# 64-pinHTSSOP.net
KiCad netlist of a schematic drawn in EAGLE
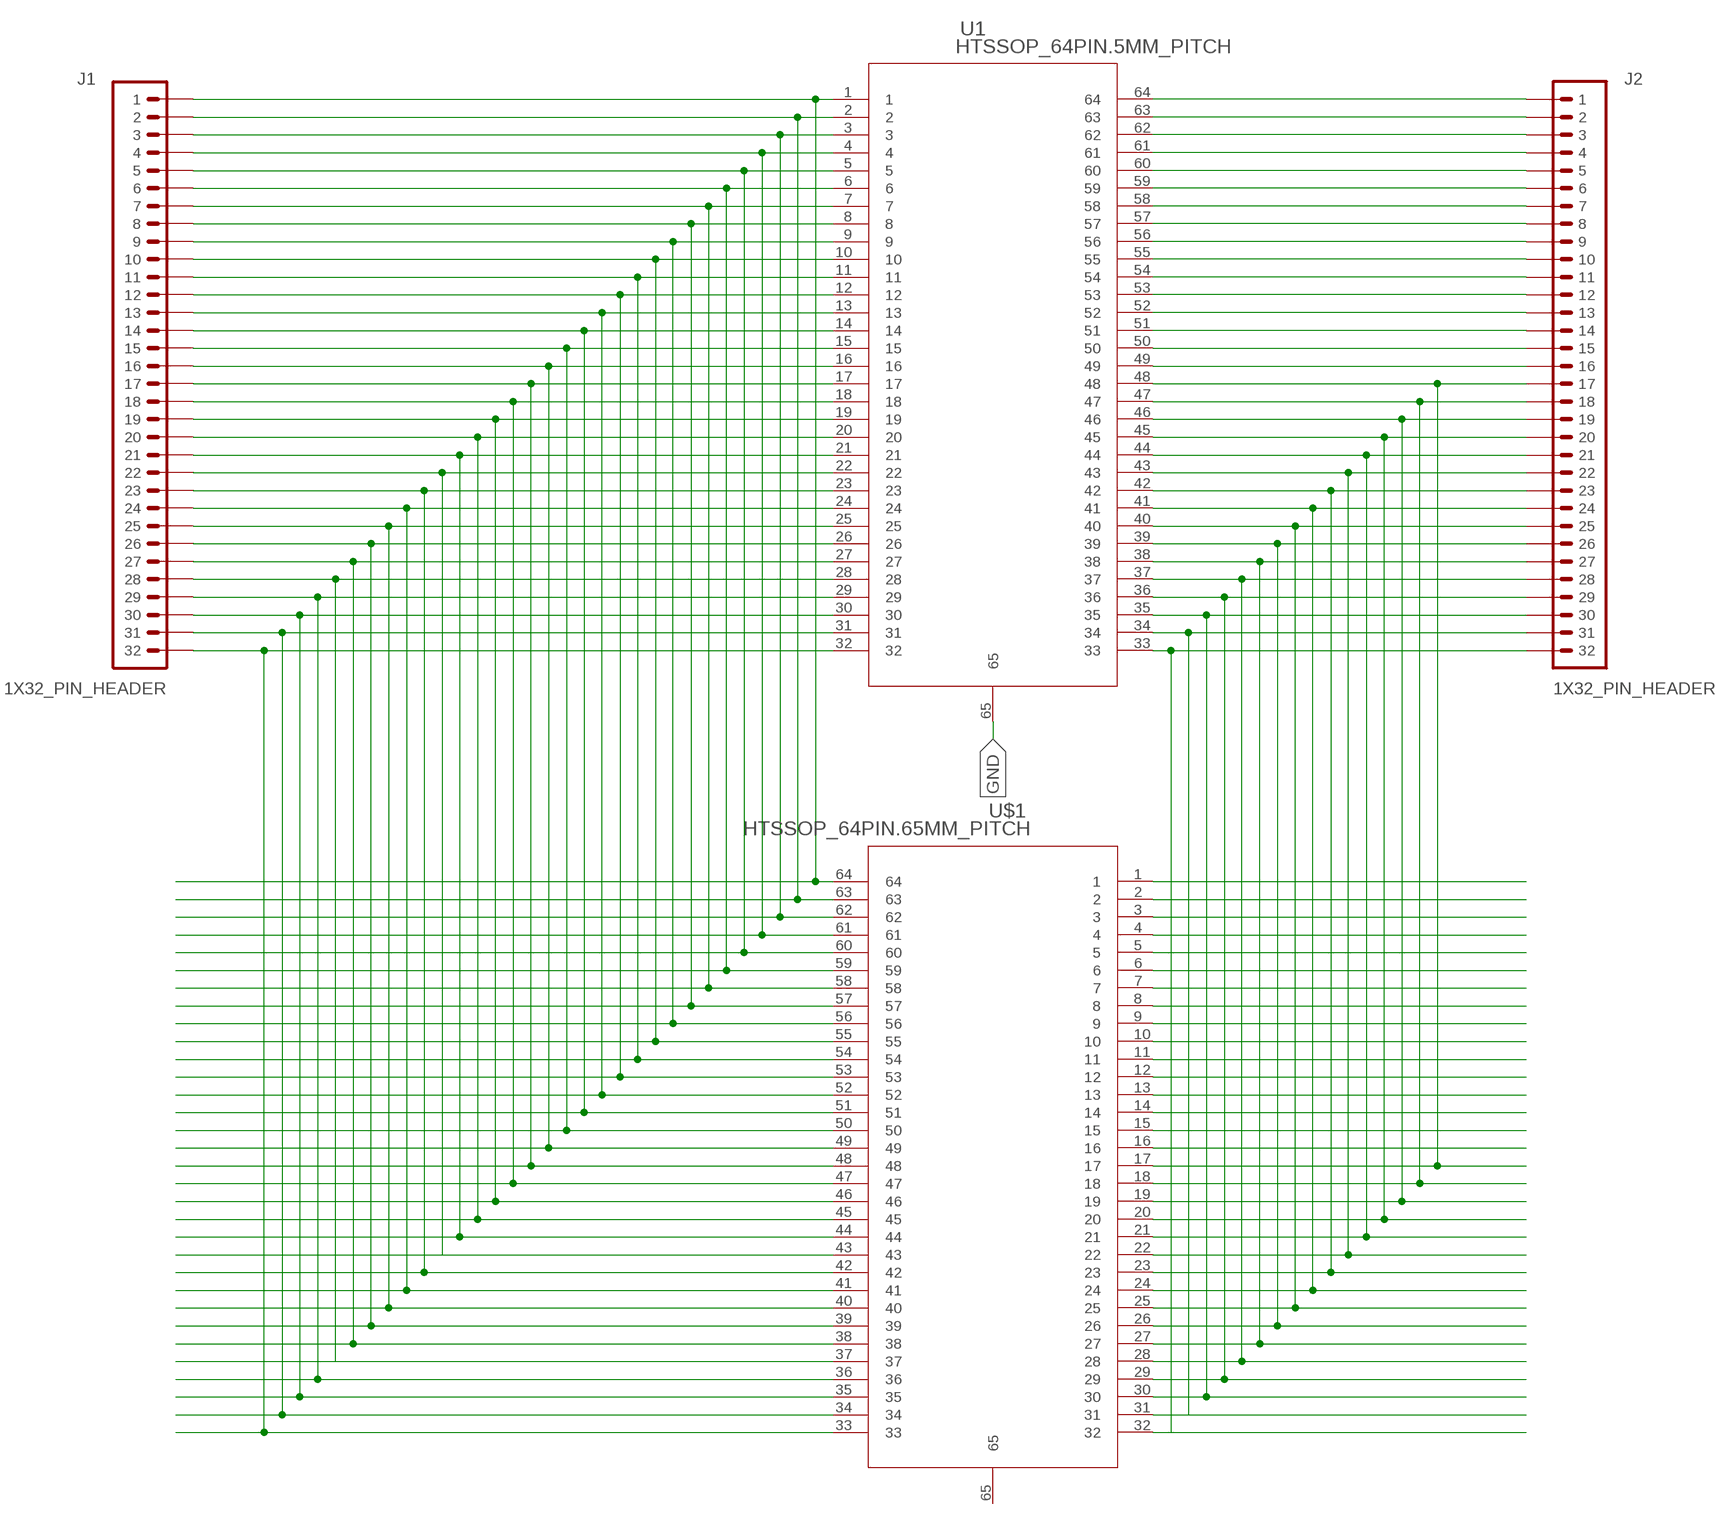
[diagram p0: schematic, sheet 1]

(export (version "E")
  (design (tool "Eeschema 10.0.6"))
  (components
    (comp (ref "J1")
      (value "1X32_PIN_HEADER")
      (footprint "eagle-import:1X32PIN")
      (libsource (lib "eagle-import") (part "1X32_PIN_HEADER"))
    )
    (comp (ref "J2")
      (value "1X32_PIN_HEADER")
      (footprint "eagle-import:1X32PIN")
      (libsource (lib "eagle-import") (part "1X32_PIN_HEADER"))
    )
    (comp (ref "U$1")
      (value "HTSSOP_64PIN.65MM_PITCH")
      (footprint "eagle-import:HTSSOP_64PIN_.65MM")
      (libsource (lib "eagle-import") (part "HTSSOP_64PIN.65MM_PITCH"))
    )
    (comp (ref "U1")
      (value "HTSSOP_64PIN.5MM_PITCH")
      (footprint "eagle-import:HTSSOP_64PIN_.5MM")
      (libsource (lib "eagle-import") (part "HTSSOP_64PIN.5MM_PITCH"))
    )
  )
  (nets
    (net (code "1") (name "GND") (class "Default")
      (node (ref "U1") (pin "65") (pinfunction "65_65") (pintype "bidirectional"))
    )
    (net (code "2") (name "Net-(J1-Pad1)") (class "Default")
      (node (ref "J1") (pin "1") (pinfunction "1_1") (pintype "passive"))
      (node (ref "U$1") (pin "64") (pinfunction "64_64") (pintype "bidirectional"))
      (node (ref "U1") (pin "1") (pinfunction "1_1") (pintype "bidirectional"))
    )
    (net (code "3") (name "Net-(J1-Pad2)") (class "Default")
      (node (ref "J1") (pin "2") (pinfunction "2_2") (pintype "passive"))
      (node (ref "U$1") (pin "63") (pinfunction "63_63") (pintype "bidirectional"))
      (node (ref "U1") (pin "2") (pinfunction "2_2") (pintype "bidirectional"))
    )
    (net (code "4") (name "Net-(J1-Pad3)") (class "Default")
      (node (ref "J1") (pin "3") (pinfunction "3_3") (pintype "passive"))
      (node (ref "U$1") (pin "62") (pinfunction "62_62") (pintype "bidirectional"))
      (node (ref "U1") (pin "3") (pinfunction "3_3") (pintype "bidirectional"))
    )
    (net (code "5") (name "Net-(J1-Pad4)") (class "Default")
      (node (ref "J1") (pin "4") (pinfunction "4_4") (pintype "passive"))
      (node (ref "U$1") (pin "61") (pinfunction "61_61") (pintype "bidirectional"))
      (node (ref "U1") (pin "4") (pinfunction "4_4") (pintype "bidirectional"))
    )
    (net (code "6") (name "Net-(J1-Pad5)") (class "Default")
      (node (ref "J1") (pin "5") (pinfunction "5_5") (pintype "passive"))
      (node (ref "U$1") (pin "60") (pinfunction "60_60") (pintype "bidirectional"))
      (node (ref "U1") (pin "5") (pinfunction "5_5") (pintype "bidirectional"))
    )
    (net (code "7") (name "Net-(J1-Pad6)") (class "Default")
      (node (ref "J1") (pin "6") (pinfunction "6_6") (pintype "passive"))
      (node (ref "U$1") (pin "59") (pinfunction "59_59") (pintype "bidirectional"))
      (node (ref "U1") (pin "6") (pinfunction "6_6") (pintype "bidirectional"))
    )
    (net (code "8") (name "Net-(J1-Pad7)") (class "Default")
      (node (ref "J1") (pin "7") (pinfunction "7_7") (pintype "passive"))
      (node (ref "U$1") (pin "58") (pinfunction "58_58") (pintype "bidirectional"))
      (node (ref "U1") (pin "7") (pinfunction "7_7") (pintype "bidirectional"))
    )
    (net (code "9") (name "Net-(J1-Pad8)") (class "Default")
      (node (ref "J1") (pin "8") (pinfunction "8_8") (pintype "passive"))
      (node (ref "U$1") (pin "57") (pinfunction "57_57") (pintype "bidirectional"))
      (node (ref "U1") (pin "8") (pinfunction "8_8") (pintype "bidirectional"))
    )
    (net (code "10") (name "Net-(J1-Pad9)") (class "Default")
      (node (ref "J1") (pin "9") (pinfunction "9_9") (pintype "passive"))
      (node (ref "U$1") (pin "56") (pinfunction "56_56") (pintype "bidirectional"))
      (node (ref "U1") (pin "9") (pinfunction "9_9") (pintype "bidirectional"))
    )
    (net (code "11") (name "Net-(J1-Pad10)") (class "Default")
      (node (ref "J1") (pin "10") (pinfunction "10_10") (pintype "passive"))
      (node (ref "U$1") (pin "55") (pinfunction "55_55") (pintype "bidirectional"))
      (node (ref "U1") (pin "10") (pinfunction "10_10") (pintype "bidirectional"))
    )
    (net (code "12") (name "Net-(J1-Pad11)") (class "Default")
      (node (ref "J1") (pin "11") (pinfunction "11_11") (pintype "passive"))
      (node (ref "U$1") (pin "54") (pinfunction "54_54") (pintype "bidirectional"))
      (node (ref "U1") (pin "11") (pinfunction "11_11") (pintype "bidirectional"))
    )
    (net (code "13") (name "Net-(J1-Pad12)") (class "Default")
      (node (ref "J1") (pin "12") (pinfunction "12_12") (pintype "passive"))
      (node (ref "U$1") (pin "53") (pinfunction "53_53") (pintype "bidirectional"))
      (node (ref "U1") (pin "12") (pinfunction "12_12") (pintype "bidirectional"))
    )
    (net (code "14") (name "Net-(J1-Pad13)") (class "Default")
      (node (ref "J1") (pin "13") (pinfunction "13_13") (pintype "passive"))
      (node (ref "U$1") (pin "52") (pinfunction "52_52") (pintype "bidirectional"))
      (node (ref "U1") (pin "13") (pinfunction "13_13") (pintype "bidirectional"))
    )
    (net (code "15") (name "Net-(J1-Pad14)") (class "Default")
      (node (ref "J1") (pin "14") (pinfunction "14_14") (pintype "passive"))
      (node (ref "U$1") (pin "51") (pinfunction "51_51") (pintype "bidirectional"))
      (node (ref "U1") (pin "14") (pinfunction "14_14") (pintype "bidirectional"))
    )
    (net (code "16") (name "Net-(J1-Pad15)") (class "Default")
      (node (ref "J1") (pin "15") (pinfunction "15_15") (pintype "passive"))
      (node (ref "U$1") (pin "50") (pinfunction "50_50") (pintype "bidirectional"))
      (node (ref "U1") (pin "15") (pinfunction "15_15") (pintype "bidirectional"))
    )
    (net (code "17") (name "Net-(J1-Pad16)") (class "Default")
      (node (ref "J1") (pin "16") (pinfunction "16_16") (pintype "passive"))
      (node (ref "U$1") (pin "49") (pinfunction "49_49") (pintype "bidirectional"))
      (node (ref "U1") (pin "16") (pinfunction "16_16") (pintype "bidirectional"))
    )
    (net (code "18") (name "Net-(J1-Pad17)") (class "Default")
      (node (ref "J1") (pin "17") (pinfunction "17_17") (pintype "passive"))
      (node (ref "U$1") (pin "48") (pinfunction "48_48") (pintype "bidirectional"))
      (node (ref "U1") (pin "17") (pinfunction "17_17") (pintype "bidirectional"))
    )
    (net (code "19") (name "Net-(J1-Pad18)") (class "Default")
      (node (ref "J1") (pin "18") (pinfunction "18_18") (pintype "passive"))
      (node (ref "U$1") (pin "47") (pinfunction "47_47") (pintype "bidirectional"))
      (node (ref "U1") (pin "18") (pinfunction "18_18") (pintype "bidirectional"))
    )
    (net (code "20") (name "Net-(J1-Pad19)") (class "Default")
      (node (ref "J1") (pin "19") (pinfunction "19_19") (pintype "passive"))
      (node (ref "U$1") (pin "46") (pinfunction "46_46") (pintype "bidirectional"))
      (node (ref "U1") (pin "19") (pinfunction "19_19") (pintype "bidirectional"))
    )
    (net (code "21") (name "Net-(J1-Pad20)") (class "Default")
      (node (ref "J1") (pin "20") (pinfunction "20_20") (pintype "passive"))
      (node (ref "U$1") (pin "45") (pinfunction "45_45") (pintype "bidirectional"))
      (node (ref "U1") (pin "20") (pinfunction "20_20") (pintype "bidirectional"))
    )
    (net (code "22") (name "Net-(J1-Pad21)") (class "Default")
      (node (ref "J1") (pin "21") (pinfunction "21_21") (pintype "passive"))
      (node (ref "U$1") (pin "44") (pinfunction "44_44") (pintype "bidirectional"))
      (node (ref "U1") (pin "21") (pinfunction "21_21") (pintype "bidirectional"))
    )
    (net (code "23") (name "Net-(J1-Pad22)") (class "Default")
      (node (ref "J1") (pin "22") (pinfunction "22_22") (pintype "passive"))
      (node (ref "U$1") (pin "43") (pinfunction "43_43") (pintype "bidirectional"))
      (node (ref "U1") (pin "22") (pinfunction "22_22") (pintype "bidirectional"))
    )
    (net (code "24") (name "Net-(J1-Pad23)") (class "Default")
      (node (ref "J1") (pin "23") (pinfunction "23_23") (pintype "passive"))
      (node (ref "U$1") (pin "42") (pinfunction "42_42") (pintype "bidirectional"))
      (node (ref "U1") (pin "23") (pinfunction "23_23") (pintype "bidirectional"))
    )
    (net (code "25") (name "Net-(J1-Pad24)") (class "Default")
      (node (ref "J1") (pin "24") (pinfunction "24_24") (pintype "passive"))
      (node (ref "U$1") (pin "41") (pinfunction "41_41") (pintype "bidirectional"))
      (node (ref "U1") (pin "24") (pinfunction "24_24") (pintype "bidirectional"))
    )
    (net (code "26") (name "Net-(J1-Pad25)") (class "Default")
      (node (ref "J1") (pin "25") (pinfunction "25_25") (pintype "passive"))
      (node (ref "U$1") (pin "40") (pinfunction "40_40") (pintype "bidirectional"))
      (node (ref "U1") (pin "25") (pinfunction "25_25") (pintype "bidirectional"))
    )
    (net (code "27") (name "Net-(J1-Pad26)") (class "Default")
      (node (ref "J1") (pin "26") (pinfunction "26_26") (pintype "passive"))
      (node (ref "U$1") (pin "39") (pinfunction "39_39") (pintype "bidirectional"))
      (node (ref "U1") (pin "26") (pinfunction "26_26") (pintype "bidirectional"))
    )
    (net (code "28") (name "Net-(J1-Pad27)") (class "Default")
      (node (ref "J1") (pin "27") (pinfunction "27_27") (pintype "passive"))
      (node (ref "U$1") (pin "38") (pinfunction "38_38") (pintype "bidirectional"))
      (node (ref "U1") (pin "27") (pinfunction "27_27") (pintype "bidirectional"))
    )
    (net (code "29") (name "Net-(J1-Pad28)") (class "Default")
      (node (ref "J1") (pin "28") (pinfunction "28_28") (pintype "passive"))
      (node (ref "U$1") (pin "37") (pinfunction "37_37") (pintype "bidirectional"))
      (node (ref "U1") (pin "28") (pinfunction "28_28") (pintype "bidirectional"))
    )
    (net (code "30") (name "Net-(J1-Pad29)") (class "Default")
      (node (ref "J1") (pin "29") (pinfunction "29_29") (pintype "passive"))
      (node (ref "U$1") (pin "36") (pinfunction "36_36") (pintype "bidirectional"))
      (node (ref "U1") (pin "29") (pinfunction "29_29") (pintype "bidirectional"))
    )
    (net (code "31") (name "Net-(J1-Pad30)") (class "Default")
      (node (ref "J1") (pin "30") (pinfunction "30_30") (pintype "passive"))
      (node (ref "U$1") (pin "35") (pinfunction "35_35") (pintype "bidirectional"))
      (node (ref "U1") (pin "30") (pinfunction "30_30") (pintype "bidirectional"))
    )
    (net (code "32") (name "Net-(J1-Pad31)") (class "Default")
      (node (ref "J1") (pin "31") (pinfunction "31_31") (pintype "passive"))
      (node (ref "U$1") (pin "34") (pinfunction "34_34") (pintype "bidirectional"))
      (node (ref "U1") (pin "31") (pinfunction "31_31") (pintype "bidirectional"))
    )
    (net (code "33") (name "Net-(J1-Pad32)") (class "Default")
      (node (ref "J1") (pin "32") (pinfunction "32_32") (pintype "passive"))
      (node (ref "U$1") (pin "33") (pinfunction "33_33") (pintype "bidirectional"))
      (node (ref "U1") (pin "32") (pinfunction "32_32") (pintype "bidirectional"))
    )
    (net (code "34") (name "Net-(J2-Pad1)") (class "Default")
      (node (ref "J2") (pin "1") (pinfunction "1_1") (pintype "passive"))
      (node (ref "U1") (pin "64") (pinfunction "64_64") (pintype "bidirectional"))
    )
    (net (code "35") (name "Net-(J2-Pad2)") (class "Default")
      (node (ref "J2") (pin "2") (pinfunction "2_2") (pintype "passive"))
      (node (ref "U1") (pin "63") (pinfunction "63_63") (pintype "bidirectional"))
    )
    (net (code "36") (name "Net-(J2-Pad3)") (class "Default")
      (node (ref "J2") (pin "3") (pinfunction "3_3") (pintype "passive"))
      (node (ref "U1") (pin "62") (pinfunction "62_62") (pintype "bidirectional"))
    )
    (net (code "37") (name "Net-(J2-Pad4)") (class "Default")
      (node (ref "J2") (pin "4") (pinfunction "4_4") (pintype "passive"))
      (node (ref "U1") (pin "61") (pinfunction "61_61") (pintype "bidirectional"))
    )
    (net (code "38") (name "Net-(J2-Pad5)") (class "Default")
      (node (ref "J2") (pin "5") (pinfunction "5_5") (pintype "passive"))
      (node (ref "U1") (pin "60") (pinfunction "60_60") (pintype "bidirectional"))
    )
    (net (code "39") (name "Net-(J2-Pad6)") (class "Default")
      (node (ref "J2") (pin "6") (pinfunction "6_6") (pintype "passive"))
      (node (ref "U1") (pin "59") (pinfunction "59_59") (pintype "bidirectional"))
    )
    (net (code "40") (name "Net-(J2-Pad7)") (class "Default")
      (node (ref "J2") (pin "7") (pinfunction "7_7") (pintype "passive"))
      (node (ref "U1") (pin "58") (pinfunction "58_58") (pintype "bidirectional"))
    )
    (net (code "41") (name "Net-(J2-Pad8)") (class "Default")
      (node (ref "J2") (pin "8") (pinfunction "8_8") (pintype "passive"))
      (node (ref "U1") (pin "57") (pinfunction "57_57") (pintype "bidirectional"))
    )
    (net (code "42") (name "Net-(J2-Pad9)") (class "Default")
      (node (ref "J2") (pin "9") (pinfunction "9_9") (pintype "passive"))
      (node (ref "U1") (pin "56") (pinfunction "56_56") (pintype "bidirectional"))
    )
    (net (code "43") (name "Net-(J2-Pad10)") (class "Default")
      (node (ref "J2") (pin "10") (pinfunction "10_10") (pintype "passive"))
      (node (ref "U1") (pin "55") (pinfunction "55_55") (pintype "bidirectional"))
    )
    (net (code "44") (name "Net-(J2-Pad11)") (class "Default")
      (node (ref "J2") (pin "11") (pinfunction "11_11") (pintype "passive"))
      (node (ref "U1") (pin "54") (pinfunction "54_54") (pintype "bidirectional"))
    )
    (net (code "45") (name "Net-(J2-Pad12)") (class "Default")
      (node (ref "J2") (pin "12") (pinfunction "12_12") (pintype "passive"))
      (node (ref "U1") (pin "53") (pinfunction "53_53") (pintype "bidirectional"))
    )
    (net (code "46") (name "Net-(J2-Pad13)") (class "Default")
      (node (ref "J2") (pin "13") (pinfunction "13_13") (pintype "passive"))
      (node (ref "U1") (pin "52") (pinfunction "52_52") (pintype "bidirectional"))
    )
    (net (code "47") (name "Net-(J2-Pad14)") (class "Default")
      (node (ref "J2") (pin "14") (pinfunction "14_14") (pintype "passive"))
      (node (ref "U1") (pin "51") (pinfunction "51_51") (pintype "bidirectional"))
    )
    (net (code "48") (name "Net-(J2-Pad15)") (class "Default")
      (node (ref "J2") (pin "15") (pinfunction "15_15") (pintype "passive"))
      (node (ref "U1") (pin "50") (pinfunction "50_50") (pintype "bidirectional"))
    )
    (net (code "49") (name "Net-(J2-Pad16)") (class "Default")
      (node (ref "J2") (pin "16") (pinfunction "16_16") (pintype "passive"))
      (node (ref "U1") (pin "49") (pinfunction "49_49") (pintype "bidirectional"))
    )
    (net (code "50") (name "Net-(J2-Pad17)") (class "Default")
      (node (ref "J2") (pin "17") (pinfunction "17_17") (pintype "passive"))
      (node (ref "U$1") (pin "17") (pinfunction "17_17") (pintype "bidirectional"))
      (node (ref "U1") (pin "48") (pinfunction "48_48") (pintype "bidirectional"))
    )
    (net (code "51") (name "Net-(J2-Pad18)") (class "Default")
      (node (ref "J2") (pin "18") (pinfunction "18_18") (pintype "passive"))
      (node (ref "U$1") (pin "18") (pinfunction "18_18") (pintype "bidirectional"))
      (node (ref "U1") (pin "47") (pinfunction "47_47") (pintype "bidirectional"))
    )
    (net (code "52") (name "Net-(J2-Pad19)") (class "Default")
      (node (ref "J2") (pin "19") (pinfunction "19_19") (pintype "passive"))
      (node (ref "U$1") (pin "19") (pinfunction "19_19") (pintype "bidirectional"))
      (node (ref "U1") (pin "46") (pinfunction "46_46") (pintype "bidirectional"))
    )
    (net (code "53") (name "Net-(J2-Pad20)") (class "Default")
      (node (ref "J2") (pin "20") (pinfunction "20_20") (pintype "passive"))
      (node (ref "U$1") (pin "20") (pinfunction "20_20") (pintype "bidirectional"))
      (node (ref "U1") (pin "45") (pinfunction "45_45") (pintype "bidirectional"))
    )
    (net (code "54") (name "Net-(J2-Pad21)") (class "Default")
      (node (ref "J2") (pin "21") (pinfunction "21_21") (pintype "passive"))
      (node (ref "U$1") (pin "21") (pinfunction "21_21") (pintype "bidirectional"))
      (node (ref "U1") (pin "44") (pinfunction "44_44") (pintype "bidirectional"))
    )
    (net (code "55") (name "Net-(J2-Pad22)") (class "Default")
      (node (ref "J2") (pin "22") (pinfunction "22_22") (pintype "passive"))
      (node (ref "U$1") (pin "22") (pinfunction "22_22") (pintype "bidirectional"))
      (node (ref "U1") (pin "43") (pinfunction "43_43") (pintype "bidirectional"))
    )
    (net (code "56") (name "Net-(J2-Pad23)") (class "Default")
      (node (ref "J2") (pin "23") (pinfunction "23_23") (pintype "passive"))
      (node (ref "U$1") (pin "23") (pinfunction "23_23") (pintype "bidirectional"))
      (node (ref "U1") (pin "42") (pinfunction "42_42") (pintype "bidirectional"))
    )
    (net (code "57") (name "Net-(J2-Pad24)") (class "Default")
      (node (ref "J2") (pin "24") (pinfunction "24_24") (pintype "passive"))
      (node (ref "U$1") (pin "24") (pinfunction "24_24") (pintype "bidirectional"))
      (node (ref "U1") (pin "41") (pinfunction "41_41") (pintype "bidirectional"))
    )
    (net (code "58") (name "Net-(J2-Pad25)") (class "Default")
      (node (ref "J2") (pin "25") (pinfunction "25_25") (pintype "passive"))
      (node (ref "U$1") (pin "25") (pinfunction "25_25") (pintype "bidirectional"))
      (node (ref "U1") (pin "40") (pinfunction "40_40") (pintype "bidirectional"))
    )
    (net (code "59") (name "Net-(J2-Pad26)") (class "Default")
      (node (ref "J2") (pin "26") (pinfunction "26_26") (pintype "passive"))
      (node (ref "U$1") (pin "26") (pinfunction "26_26") (pintype "bidirectional"))
      (node (ref "U1") (pin "39") (pinfunction "39_39") (pintype "bidirectional"))
    )
    (net (code "60") (name "Net-(J2-Pad27)") (class "Default")
      (node (ref "J2") (pin "27") (pinfunction "27_27") (pintype "passive"))
      (node (ref "U$1") (pin "27") (pinfunction "27_27") (pintype "bidirectional"))
      (node (ref "U1") (pin "38") (pinfunction "38_38") (pintype "bidirectional"))
    )
    (net (code "61") (name "Net-(J2-Pad28)") (class "Default")
      (node (ref "J2") (pin "28") (pinfunction "28_28") (pintype "passive"))
      (node (ref "U$1") (pin "28") (pinfunction "28_28") (pintype "bidirectional"))
      (node (ref "U1") (pin "37") (pinfunction "37_37") (pintype "bidirectional"))
    )
    (net (code "62") (name "Net-(J2-Pad29)") (class "Default")
      (node (ref "J2") (pin "29") (pinfunction "29_29") (pintype "passive"))
      (node (ref "U$1") (pin "29") (pinfunction "29_29") (pintype "bidirectional"))
      (node (ref "U1") (pin "36") (pinfunction "36_36") (pintype "bidirectional"))
    )
    (net (code "63") (name "Net-(J2-Pad30)") (class "Default")
      (node (ref "J2") (pin "30") (pinfunction "30_30") (pintype "passive"))
      (node (ref "U$1") (pin "30") (pinfunction "30_30") (pintype "bidirectional"))
      (node (ref "U1") (pin "35") (pinfunction "35_35") (pintype "bidirectional"))
    )
    (net (code "64") (name "Net-(J2-Pad31)") (class "Default")
      (node (ref "J2") (pin "31") (pinfunction "31_31") (pintype "passive"))
      (node (ref "U$1") (pin "31") (pinfunction "31_31") (pintype "bidirectional"))
      (node (ref "U1") (pin "34") (pinfunction "34_34") (pintype "bidirectional"))
    )
    (net (code "65") (name "Net-(J2-Pad32)") (class "Default")
      (node (ref "J2") (pin "32") (pinfunction "32_32") (pintype "passive"))
      (node (ref "U$1") (pin "32") (pinfunction "32_32") (pintype "bidirectional"))
      (node (ref "U1") (pin "33") (pinfunction "33_33") (pintype "bidirectional"))
    )
    (net (code "66") (name "unconnected-(U$1-Pad1)") (class "Default")
      (node (ref "U$1") (pin "1") (pinfunction "1_1") (pintype "bidirectional"))
    )
    (net (code "67") (name "unconnected-(U$1-Pad2)") (class "Default")
      (node (ref "U$1") (pin "2") (pinfunction "2_2") (pintype "bidirectional"))
    )
    (net (code "68") (name "unconnected-(U$1-Pad3)") (class "Default")
      (node (ref "U$1") (pin "3") (pinfunction "3_3") (pintype "bidirectional"))
    )
    (net (code "69") (name "unconnected-(U$1-Pad4)") (class "Default")
      (node (ref "U$1") (pin "4") (pinfunction "4_4") (pintype "bidirectional"))
    )
    (net (code "70") (name "unconnected-(U$1-Pad5)") (class "Default")
      (node (ref "U$1") (pin "5") (pinfunction "5_5") (pintype "bidirectional"))
    )
    (net (code "71") (name "unconnected-(U$1-Pad6)") (class "Default")
      (node (ref "U$1") (pin "6") (pinfunction "6_6") (pintype "bidirectional"))
    )
    (net (code "72") (name "unconnected-(U$1-Pad7)") (class "Default")
      (node (ref "U$1") (pin "7") (pinfunction "7_7") (pintype "bidirectional"))
    )
    (net (code "73") (name "unconnected-(U$1-Pad8)") (class "Default")
      (node (ref "U$1") (pin "8") (pinfunction "8_8") (pintype "bidirectional"))
    )
    (net (code "74") (name "unconnected-(U$1-Pad9)") (class "Default")
      (node (ref "U$1") (pin "9") (pinfunction "9_9") (pintype "bidirectional"))
    )
    (net (code "75") (name "unconnected-(U$1-Pad10)") (class "Default")
      (node (ref "U$1") (pin "10") (pinfunction "10_10") (pintype "bidirectional"))
    )
    (net (code "76") (name "unconnected-(U$1-Pad11)") (class "Default")
      (node (ref "U$1") (pin "11") (pinfunction "11_11") (pintype "bidirectional"))
    )
    (net (code "77") (name "unconnected-(U$1-Pad12)") (class "Default")
      (node (ref "U$1") (pin "12") (pinfunction "12_12") (pintype "bidirectional"))
    )
    (net (code "78") (name "unconnected-(U$1-Pad13)") (class "Default")
      (node (ref "U$1") (pin "13") (pinfunction "13_13") (pintype "bidirectional"))
    )
    (net (code "79") (name "unconnected-(U$1-Pad14)") (class "Default")
      (node (ref "U$1") (pin "14") (pinfunction "14_14") (pintype "bidirectional"))
    )
    (net (code "80") (name "unconnected-(U$1-Pad15)") (class "Default")
      (node (ref "U$1") (pin "15") (pinfunction "15_15") (pintype "bidirectional"))
    )
    (net (code "81") (name "unconnected-(U$1-Pad16)") (class "Default")
      (node (ref "U$1") (pin "16") (pinfunction "16_16") (pintype "bidirectional"))
    )
    (net (code "82") (name "unconnected-(U$1-Pad65)") (class "Default")
      (node (ref "U$1") (pin "65") (pinfunction "65_65") (pintype "bidirectional"))
    )
  )
)
